# communication_module_20190805.net
KiCad netlist of a schematic drawn in EAGLE
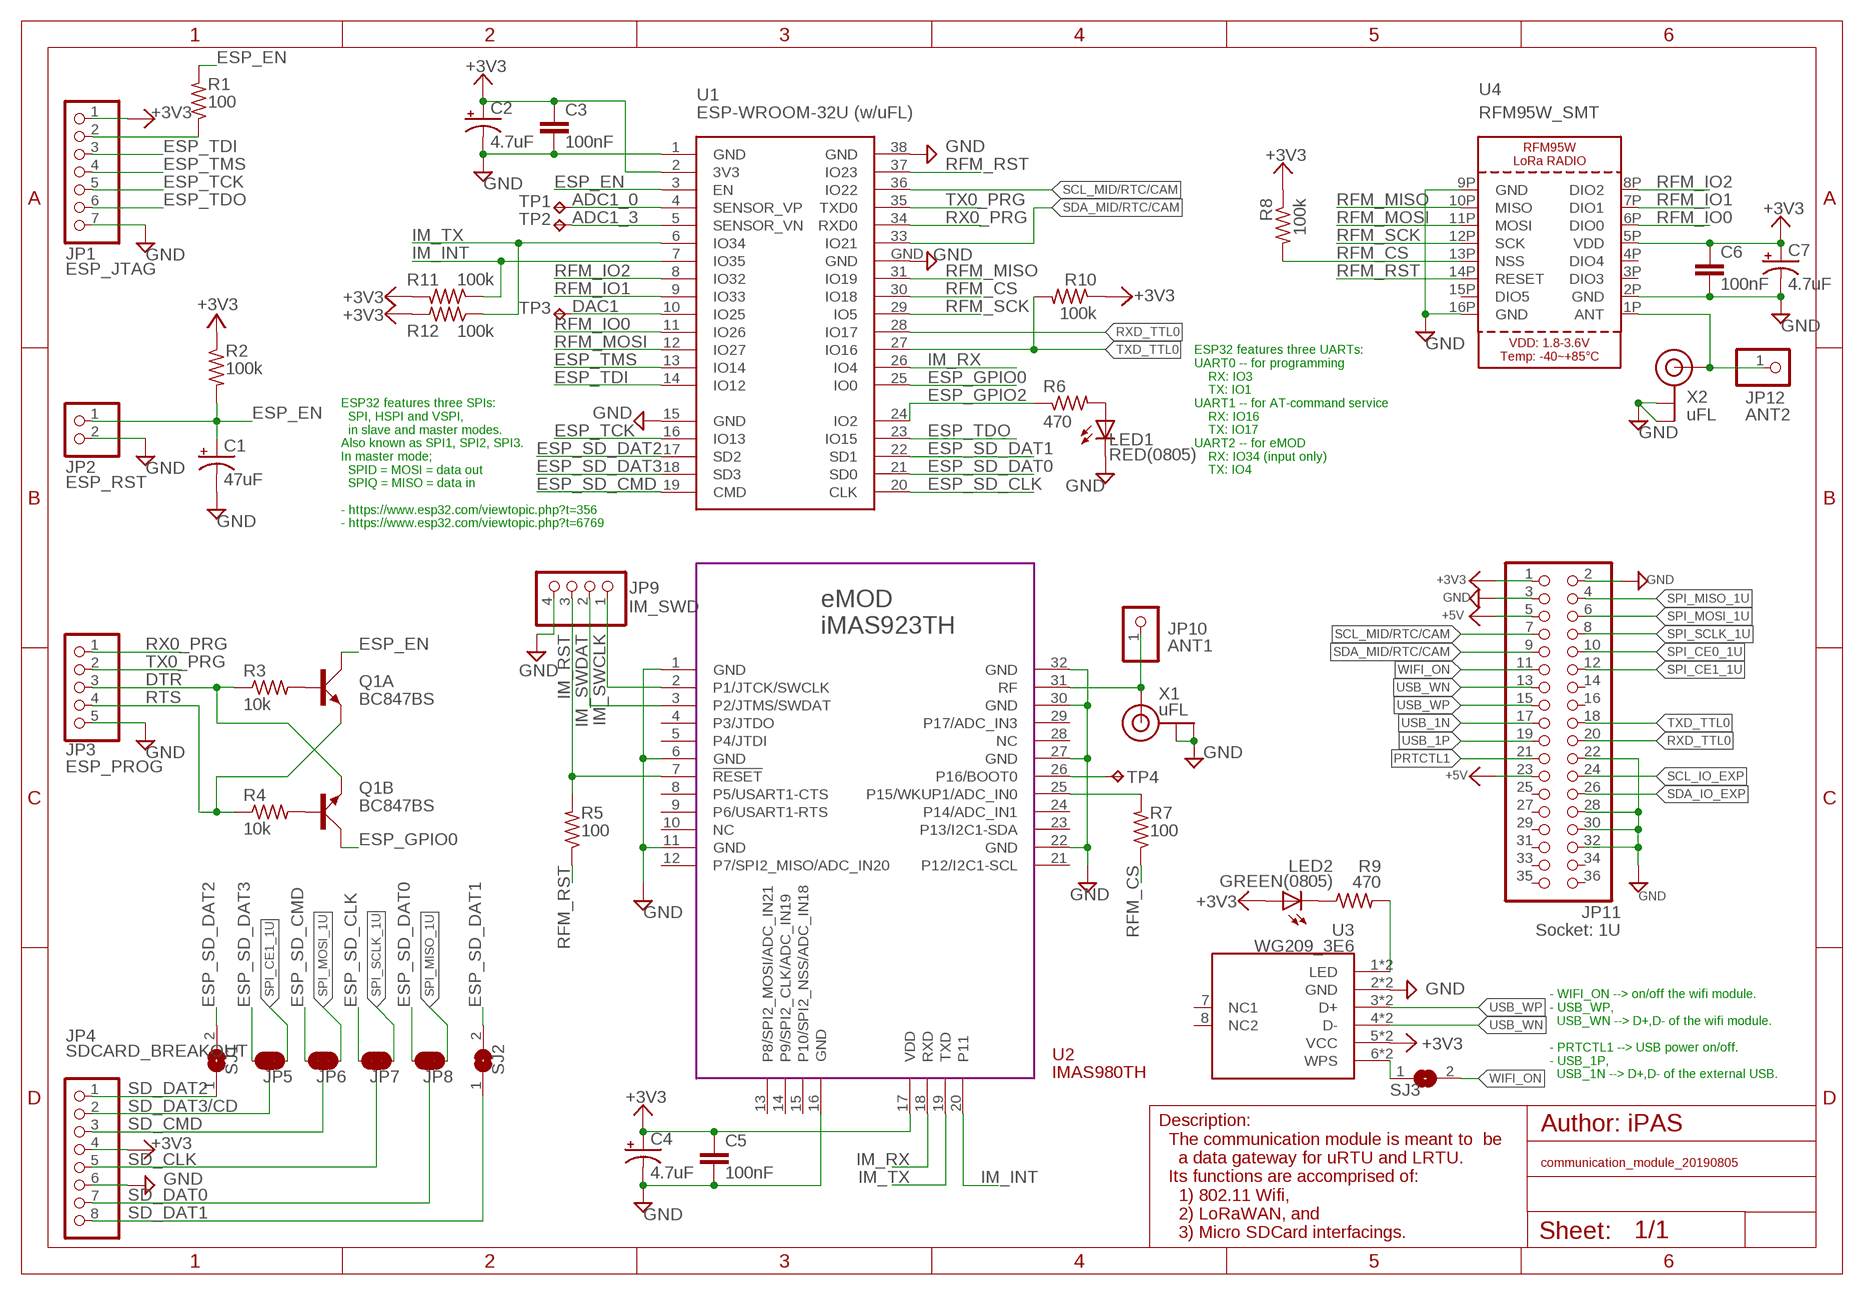
[diagram p0: schematic, sheet 1]

(export (version "E")
  (design (tool "Eeschema 10.0.6"))
  (components
    (comp (ref "C1")
      (value "47uF")
      (footprint "eagle-import:RCL_150CLZ-1014")
      (libsource (lib "eagle-import") (part "RCL_CPOL-US150CLZ-1014"))
    )
    (comp (ref "C2")
      (value "4.7uF")
      (footprint "eagle-import:RCL_150CLZ-1014")
      (libsource (lib "eagle-import") (part "RCL_CPOL-US150CLZ-1014"))
    )
    (comp (ref "C3")
      (value "100nF")
      (footprint "eagle-import:RCL_C1206")
      (libsource (lib "eagle-import") (part "RCL_C-EUC1206"))
    )
    (comp (ref "C4")
      (value "4.7uF")
      (footprint "eagle-import:RCL_150CLZ-1014")
      (libsource (lib "eagle-import") (part "RCL_CPOL-US150CLZ-1014"))
    )
    (comp (ref "C5")
      (value "100nF")
      (footprint "eagle-import:RCL_C1206")
      (libsource (lib "eagle-import") (part "RCL_C-EUC1206"))
    )
    (comp (ref "C6")
      (value "100nF")
      (footprint "eagle-import:RCL_C1206")
      (libsource (lib "eagle-import") (part "RCL_C-EUC1206"))
    )
    (comp (ref "C7")
      (value "4.7uF")
      (footprint "eagle-import:RCL_150CLZ-1014")
      (libsource (lib "eagle-import") (part "RCL_CPOL-US150CLZ-1014"))
    )
    (comp (ref "JP1")
      (value "ESP_JTAG")
      (footprint "eagle-import:1X07")
      (libsource (lib "eagle-import") (part "PINHD-1X7"))
    )
    (comp (ref "JP2")
      (value "ESP_RST")
      (footprint "eagle-import:1X02")
      (libsource (lib "eagle-import") (part "PINHD-1X2"))
    )
    (comp (ref "JP3")
      (value "ESP_PROG")
      (footprint "eagle-import:1X05")
      (libsource (lib "eagle-import") (part "PINHD-1X5"))
    )
    (comp (ref "JP4")
      (value "SDCARD_BREAKOUT")
      (footprint "eagle-import:1X08")
      (libsource (lib "eagle-import") (part "PINHD-1X8"))
    )
    (comp (ref "JP5")
      (value "JUMPER-SMT_3_NO_NO-SILK")
      (footprint "eagle-import:SMT-JUMPER_3_NO_NO-SILK")
      (libsource (lib "eagle-import") (part "JUMPER-SMT_3_NO_NO-SILK"))
    )
    (comp (ref "JP6")
      (value "JUMPER-SMT_3_NO_NO-SILK")
      (footprint "eagle-import:SMT-JUMPER_3_NO_NO-SILK")
      (libsource (lib "eagle-import") (part "JUMPER-SMT_3_NO_NO-SILK"))
    )
    (comp (ref "JP7")
      (value "JUMPER-SMT_3_NO_NO-SILK")
      (footprint "eagle-import:SMT-JUMPER_3_NO_NO-SILK")
      (libsource (lib "eagle-import") (part "JUMPER-SMT_3_NO_NO-SILK"))
    )
    (comp (ref "JP8")
      (value "JUMPER-SMT_3_NO_NO-SILK")
      (footprint "eagle-import:SMT-JUMPER_3_NO_NO-SILK")
      (libsource (lib "eagle-import") (part "JUMPER-SMT_3_NO_NO-SILK"))
    )
    (comp (ref "JP9")
      (value "IM_SWD")
      (footprint "eagle-import:1X04")
      (libsource (lib "eagle-import") (part "PINHD-1X4"))
    )
    (comp (ref "JP10")
      (value "ANT1")
      (footprint "eagle-import:1X01_ROUND")
      (libsource (lib "eagle-import") (part "HEADER-1X1ROUND"))
    )
    (comp (ref "JP11")
      (value "Socket: 1U")
      (footprint "eagle-import:2X18")
      (libsource (lib "eagle-import") (part "PINHD-2X18"))
    )
    (comp (ref "JP12")
      (value "ANT2")
      (footprint "eagle-import:1X01_ROUND")
      (libsource (lib "eagle-import") (part "HEADER-1X1ROUND"))
    )
    (comp (ref "LED1")
      (value "RED(0805)")
      (footprint "eagle-import:CHIP-LED0805")
      (libsource (lib "eagle-import") (part "LEDCHIP-LED0805"))
    )
    (comp (ref "LED2")
      (value "GREEN(0805)")
      (footprint "eagle-import:CHIP-LED0805")
      (libsource (lib "eagle-import") (part "LEDCHIP-LED0805"))
    )
    (comp (ref "Q1")
      (value "BC847BS")
      (footprint "eagle-import:SOT363_PHILIPS")
      (libsource (lib "eagle-import") (part "BC847BS"))
    )
    (comp (ref "R1")
      (value "100")
      (footprint "eagle-import:RCL_M0805")
      (libsource (lib "eagle-import") (part "RCL_R-USM0805"))
    )
    (comp (ref "R2")
      (value "100k")
      (footprint "eagle-import:RCL_M0805")
      (libsource (lib "eagle-import") (part "RCL_R-USM0805"))
    )
    (comp (ref "R3")
      (value "10k")
      (footprint "eagle-import:RCL_M0805")
      (libsource (lib "eagle-import") (part "RCL_R-USM0805"))
    )
    (comp (ref "R4")
      (value "10k")
      (footprint "eagle-import:RCL_M0805")
      (libsource (lib "eagle-import") (part "RCL_R-USM0805"))
    )
    (comp (ref "R5")
      (value "100")
      (footprint "eagle-import:RCL_M0805")
      (libsource (lib "eagle-import") (part "RCL_R-USM0805"))
    )
    (comp (ref "R6")
      (value "470")
      (footprint "eagle-import:RCL_M0805")
      (libsource (lib "eagle-import") (part "RCL_R-USM0805"))
    )
    (comp (ref "R7")
      (value "100")
      (footprint "eagle-import:RCL_M0805")
      (libsource (lib "eagle-import") (part "RCL_R-USM0805"))
    )
    (comp (ref "R8")
      (value "100k")
      (footprint "eagle-import:RCL_M0805")
      (libsource (lib "eagle-import") (part "RCL_R-USM0805"))
    )
    (comp (ref "R9")
      (value "470")
      (footprint "eagle-import:RCL_M0805")
      (libsource (lib "eagle-import") (part "RCL_R-USM0805"))
    )
    (comp (ref "R10")
      (value "100k")
      (footprint "eagle-import:RCL_M0805")
      (libsource (lib "eagle-import") (part "RCL_R-USM0805"))
    )
    (comp (ref "R11")
      (value "100k")
      (footprint "eagle-import:RCL_M0805")
      (libsource (lib "eagle-import") (part "RCL_R-USM0805"))
    )
    (comp (ref "R12")
      (value "100k")
      (footprint "eagle-import:RCL_M0805")
      (libsource (lib "eagle-import") (part "RCL_R-USM0805"))
    )
    (comp (ref "SJ1")
      (value "SOLDERJUMPERREFLOW")
      (footprint "eagle-import:SOLDERJUMPER_REFLOW")
      (libsource (lib "eagle-import") (part "SOLDERJUMPERREFLOW"))
    )
    (comp (ref "SJ2")
      (value "SOLDERJUMPERREFLOW")
      (footprint "eagle-import:SOLDERJUMPER_REFLOW")
      (libsource (lib "eagle-import") (part "SOLDERJUMPERREFLOW"))
    )
    (comp (ref "SJ3")
      (value "SOLDERJUMPERREFLOW")
      (footprint "eagle-import:SOLDERJUMPER_REFLOW")
      (libsource (lib "eagle-import") (part "SOLDERJUMPERREFLOW"))
    )
    (comp (ref "TP1")
      (value "TPB1,27")
      (footprint "eagle-import:B1,27")
      (libsource (lib "eagle-import") (part "TPB1,27"))
    )
    (comp (ref "TP2")
      (value "TPB1,27")
      (footprint "eagle-import:B1,27")
      (libsource (lib "eagle-import") (part "TPB1,27"))
    )
    (comp (ref "TP3")
      (value "TPB1,27")
      (footprint "eagle-import:B1,27")
      (libsource (lib "eagle-import") (part "TPB1,27"))
    )
    (comp (ref "TP4")
      (value "TPB1,27")
      (footprint "eagle-import:B1,27")
      (libsource (lib "eagle-import") (part "TPB1,27"))
    )
    (comp (ref "U1")
      (value "ESP-WROOM-32U (w/uFL)")
      (footprint "eagle-import:ESP-WROOM-32")
      (libsource (lib "eagle-import") (part "ESP-WROOM-32"))
    )
    (comp (ref "U2")
      (value "IMAS980TH")
      (footprint "eagle-import:IMAS923TH")
      (libsource (lib "eagle-import") (part "IMAS980TH"))
    )
    (comp (ref "U3")
      (value "WG209_3E6")
      (footprint "eagle-import:WG209")
      (libsource (lib "eagle-import") (part "WG209"))
    )
    (comp (ref "U4")
      (value "RFM95W_SMT")
      (footprint "eagle-import:RFMHCW_SMT")
      (libsource (lib "eagle-import") (part "RFM95W_SMT"))
    )
    (comp (ref "X1")
      (value "uFL")
      (footprint "eagle-import:U.FL")
      (libsource (lib "eagle-import") (part "ANTENNA_U.FL"))
    )
    (comp (ref "X2")
      (value "uFL")
      (footprint "eagle-import:U.FL")
      (libsource (lib "eagle-import") (part "ANTENNA_U.FL"))
    )
  )
  (nets
    (net (code "1") (name "+3V3") (class "Default")
      (node (ref "C2") (pin "+") (pinfunction "+_+") (pintype "passive"))
      (node (ref "C3") (pin "1") (pinfunction "1_1") (pintype "passive"))
      (node (ref "C4") (pin "+") (pinfunction "+_+") (pintype "passive"))
      (node (ref "C5") (pin "1") (pinfunction "1_1") (pintype "passive"))
      (node (ref "C6") (pin "1") (pinfunction "1_1") (pintype "passive"))
      (node (ref "C7") (pin "+") (pinfunction "+_+") (pintype "passive"))
      (node (ref "JP1") (pin "1") (pinfunction "1_1") (pintype "passive"))
      (node (ref "JP11") (pin "1") (pinfunction "1_1") (pintype "passive"))
      (node (ref "JP4") (pin "4") (pinfunction "4_4") (pintype "passive"))
      (node (ref "LED2") (pin "A") (pinfunction "A_A") (pintype "passive"))
      (node (ref "R10") (pin "1") (pinfunction "1_1") (pintype "passive"))
      (node (ref "R11") (pin "2") (pinfunction "2_2") (pintype "passive"))
      (node (ref "R12") (pin "2") (pinfunction "2_2") (pintype "passive"))
      (node (ref "R2") (pin "1") (pinfunction "1_1") (pintype "passive"))
      (node (ref "R8") (pin "1") (pinfunction "1_1") (pintype "passive"))
      (node (ref "U1") (pin "2") (pinfunction "3V3_2") (pintype "power_in"))
      (node (ref "U2") (pin "17") (pinfunction "VDD_17") (pintype "power_in"))
      (node (ref "U3") (pin "5") (pinfunction "VCC_5") (pintype "power_in"))
      (node (ref "U3") (pin "5P") (pinfunction "VCC_5P") (pintype "power_in"))
      (node (ref "U4") (pin "5P") (pinfunction "VDD_5P") (pintype "power_in"))
    )
    (net (code "2") (name "+5V") (class "Default")
      (node (ref "JP11") (pin "23") (pinfunction "23_23") (pintype "passive"))
      (node (ref "JP11") (pin "5") (pinfunction "5_5") (pintype "passive"))
    )
    (net (code "3") (name "/ADC1_0") (class "Default")
      (node (ref "TP1") (pin "TP") (pinfunction "TP_TP") (pintype "input"))
      (node (ref "U1") (pin "4") (pinfunction "SENSOR_VP_4") (pintype "bidirectional"))
    )
    (net (code "4") (name "/ADC1_3") (class "Default")
      (node (ref "TP2") (pin "TP") (pinfunction "TP_TP") (pintype "input"))
      (node (ref "U1") (pin "5") (pinfunction "SENSOR_VN_5") (pintype "bidirectional"))
    )
    (net (code "5") (name "/DAC1") (class "Default")
      (node (ref "TP3") (pin "TP") (pinfunction "TP_TP") (pintype "input"))
      (node (ref "U1") (pin "10") (pinfunction "IO25_10") (pintype "bidirectional"))
    )
    (net (code "6") (name "/DTR") (class "Default")
      (node (ref "JP3") (pin "3") (pinfunction "3_3") (pintype "passive"))
      (node (ref "Q1") (pin "4") (pinfunction "E_4") (pintype "passive"))
      (node (ref "R3") (pin "1") (pinfunction "1_1") (pintype "passive"))
    )
    (net (code "7") (name "/ESP_EN") (class "Default")
      (node (ref "C1") (pin "+") (pinfunction "+_+") (pintype "passive"))
      (node (ref "JP2") (pin "1") (pinfunction "1_1") (pintype "passive"))
      (node (ref "Q1") (pin "6") (pinfunction "C_6") (pintype "passive"))
      (node (ref "R1") (pin "2") (pinfunction "2_2") (pintype "passive"))
      (node (ref "R2") (pin "2") (pinfunction "2_2") (pintype "passive"))
      (node (ref "U1") (pin "3") (pinfunction "EN_3") (pintype "input"))
    )
    (net (code "8") (name "/ESP_GPIO0") (class "Default")
      (node (ref "Q1") (pin "3") (pinfunction "C_3") (pintype "passive"))
      (node (ref "U1") (pin "25") (pinfunction "IO0_25") (pintype "bidirectional"))
    )
    (net (code "9") (name "/ESP_GPIO2") (class "Default")
      (node (ref "R6") (pin "1") (pinfunction "1_1") (pintype "passive"))
      (node (ref "U1") (pin "24") (pinfunction "IO2_24") (pintype "bidirectional"))
    )
    (net (code "10") (name "/ESP_SD_CLK") (class "Default")
      (node (ref "JP7") (pin "1") (pinfunction "1_1") (pintype "passive"))
      (node (ref "U1") (pin "20") (pinfunction "CLK_20") (pintype "bidirectional"))
    )
    (net (code "11") (name "/ESP_SD_CMD") (class "Default")
      (node (ref "JP6") (pin "1") (pinfunction "1_1") (pintype "passive"))
      (node (ref "U1") (pin "19") (pinfunction "CMD_19") (pintype "bidirectional"))
    )
    (net (code "12") (name "/ESP_SD_DAT0") (class "Default")
      (node (ref "JP8") (pin "1") (pinfunction "1_1") (pintype "passive"))
      (node (ref "U1") (pin "21") (pinfunction "SD0_21") (pintype "bidirectional"))
    )
    (net (code "13") (name "/ESP_SD_DAT1") (class "Default")
      (node (ref "SJ2") (pin "2") (pinfunction "2_2") (pintype "passive"))
      (node (ref "U1") (pin "22") (pinfunction "SD1_22") (pintype "bidirectional"))
    )
    (net (code "14") (name "/ESP_SD_DAT2") (class "Default")
      (node (ref "SJ1") (pin "2") (pinfunction "2_2") (pintype "passive"))
      (node (ref "U1") (pin "17") (pinfunction "SD2_17") (pintype "bidirectional"))
    )
    (net (code "15") (name "/ESP_SD_DAT3") (class "Default")
      (node (ref "JP5") (pin "1") (pinfunction "1_1") (pintype "passive"))
      (node (ref "U1") (pin "18") (pinfunction "SD3_18") (pintype "bidirectional"))
    )
    (net (code "16") (name "/ESP_TCK") (class "Default")
      (node (ref "JP1") (pin "5") (pinfunction "5_5") (pintype "passive"))
      (node (ref "U1") (pin "16") (pinfunction "IO13_16") (pintype "bidirectional"))
    )
    (net (code "17") (name "/ESP_TDI") (class "Default")
      (node (ref "JP1") (pin "3") (pinfunction "3_3") (pintype "passive"))
      (node (ref "U1") (pin "14") (pinfunction "IO12_14") (pintype "bidirectional"))
    )
    (net (code "18") (name "/ESP_TDO") (class "Default")
      (node (ref "JP1") (pin "6") (pinfunction "6_6") (pintype "passive"))
      (node (ref "U1") (pin "23") (pinfunction "IO15_23") (pintype "bidirectional"))
    )
    (net (code "19") (name "/ESP_TMS") (class "Default")
      (node (ref "JP1") (pin "4") (pinfunction "4_4") (pintype "passive"))
      (node (ref "U1") (pin "13") (pinfunction "IO14_13") (pintype "bidirectional"))
    )
    (net (code "20") (name "/IM_INT") (class "Default")
      (node (ref "R11") (pin "1") (pinfunction "1_1") (pintype "passive"))
      (node (ref "U1") (pin "7") (pinfunction "IO35_7") (pintype "bidirectional"))
      (node (ref "U2") (pin "20") (pinfunction "P11_20") (pintype "bidirectional"))
    )
    (net (code "21") (name "/IM_RST") (class "Default")
      (node (ref "JP9") (pin "3") (pinfunction "3_3") (pintype "passive"))
      (node (ref "R5") (pin "2") (pinfunction "2_2") (pintype "passive"))
      (node (ref "U2") (pin "7") (pinfunction "~{RESET}_7") (pintype "passive"))
    )
    (net (code "22") (name "/IM_RX") (class "Default")
      (node (ref "U1") (pin "26") (pinfunction "IO4_26") (pintype "bidirectional"))
      (node (ref "U2") (pin "18") (pinfunction "RXD_18") (pintype "bidirectional"))
    )
    (net (code "23") (name "/IM_SWCLK") (class "Default")
      (node (ref "JP9") (pin "1") (pinfunction "1_1") (pintype "passive"))
      (node (ref "U2") (pin "2") (pinfunction "P1/JTCK/SWCLK_2") (pintype "bidirectional"))
    )
    (net (code "24") (name "/IM_SWDAT") (class "Default")
      (node (ref "JP9") (pin "2") (pinfunction "2_2") (pintype "passive"))
      (node (ref "U2") (pin "3") (pinfunction "P2/JTMS/SWDAT_3") (pintype "bidirectional"))
    )
    (net (code "25") (name "/IM_TX") (class "Default")
      (node (ref "R12") (pin "1") (pinfunction "1_1") (pintype "passive"))
      (node (ref "U1") (pin "6") (pinfunction "IO34_6") (pintype "bidirectional"))
      (node (ref "U2") (pin "19") (pinfunction "TXD_19") (pintype "bidirectional"))
    )
    (net (code "26") (name "/RFM_CS") (class "Default")
      (node (ref "R7") (pin "1") (pinfunction "1_1") (pintype "passive"))
      (node (ref "R8") (pin "2") (pinfunction "2_2") (pintype "passive"))
      (node (ref "U1") (pin "30") (pinfunction "IO18_30") (pintype "bidirectional"))
      (node (ref "U4") (pin "13P") (pinfunction "NSS_13P") (pintype "input"))
    )
    (net (code "27") (name "/RFM_IO0") (class "Default")
      (node (ref "U1") (pin "11") (pinfunction "IO26_11") (pintype "bidirectional"))
      (node (ref "U4") (pin "6P") (pinfunction "DIO0_6P") (pintype "bidirectional"))
    )
    (net (code "28") (name "/RFM_IO1") (class "Default")
      (node (ref "U1") (pin "9") (pinfunction "IO33_9") (pintype "bidirectional"))
      (node (ref "U4") (pin "7P") (pinfunction "DIO1_7P") (pintype "bidirectional"))
    )
    (net (code "29") (name "/RFM_IO2") (class "Default")
      (node (ref "U1") (pin "8") (pinfunction "IO32_8") (pintype "bidirectional"))
      (node (ref "U4") (pin "8P") (pinfunction "DIO2_8P") (pintype "bidirectional"))
    )
    (net (code "30") (name "/RFM_MISO") (class "Default")
      (node (ref "U1") (pin "31") (pinfunction "IO19_31") (pintype "bidirectional"))
      (node (ref "U4") (pin "10P") (pinfunction "MISO_10P") (pintype "output"))
    )
    (net (code "31") (name "/RFM_MOSI") (class "Default")
      (node (ref "U1") (pin "12") (pinfunction "IO27_12") (pintype "bidirectional"))
      (node (ref "U4") (pin "11P") (pinfunction "MOSI_11P") (pintype "input"))
    )
    (net (code "32") (name "/RFM_RST") (class "Default")
      (node (ref "R5") (pin "1") (pinfunction "1_1") (pintype "passive"))
      (node (ref "U1") (pin "37") (pinfunction "IO23_37") (pintype "bidirectional"))
      (node (ref "U4") (pin "14P") (pinfunction "RESET_14P") (pintype "input"))
    )
    (net (code "33") (name "/RFM_SCK") (class "Default")
      (node (ref "U1") (pin "29") (pinfunction "IO5_29") (pintype "bidirectional"))
      (node (ref "U4") (pin "12P") (pinfunction "SCK_12P") (pintype "input"))
    )
    (net (code "34") (name "/RTS") (class "Default")
      (node (ref "JP3") (pin "4") (pinfunction "4_4") (pintype "passive"))
      (node (ref "Q1") (pin "1") (pinfunction "E_1") (pintype "passive"))
      (node (ref "R4") (pin "1") (pinfunction "1_1") (pintype "passive"))
    )
    (net (code "35") (name "/RX0_PRG") (class "Default")
      (node (ref "JP3") (pin "1") (pinfunction "1_1") (pintype "passive"))
      (node (ref "U1") (pin "34") (pinfunction "RXD0_34") (pintype "bidirectional"))
    )
    (net (code "36") (name "/SD_CLK") (class "Default")
      (node (ref "JP4") (pin "5") (pinfunction "5_5") (pintype "passive"))
      (node (ref "JP7") (pin "2") (pinfunction "2_2") (pintype "passive"))
    )
    (net (code "37") (name "/SD_CMD") (class "Default")
      (node (ref "JP4") (pin "3") (pinfunction "3_3") (pintype "passive"))
      (node (ref "JP6") (pin "2") (pinfunction "2_2") (pintype "passive"))
    )
    (net (code "38") (name "/SD_DAT0") (class "Default")
      (node (ref "JP4") (pin "7") (pinfunction "7_7") (pintype "passive"))
      (node (ref "JP8") (pin "2") (pinfunction "2_2") (pintype "passive"))
    )
    (net (code "39") (name "/SD_DAT1") (class "Default")
      (node (ref "JP4") (pin "8") (pinfunction "8_8") (pintype "passive"))
      (node (ref "SJ2") (pin "1") (pinfunction "1_1") (pintype "passive"))
    )
    (net (code "40") (name "/SD_DAT2") (class "Default")
      (node (ref "JP4") (pin "1") (pinfunction "1_1") (pintype "passive"))
      (node (ref "SJ1") (pin "1") (pinfunction "1_1") (pintype "passive"))
    )
    (net (code "41") (name "/SD_DAT3{slash}CD") (class "Default")
      (node (ref "JP4") (pin "2") (pinfunction "2_2") (pintype "passive"))
      (node (ref "JP5") (pin "2") (pinfunction "2_2") (pintype "passive"))
    )
    (net (code "42") (name "/TX0_PRG") (class "Default")
      (node (ref "JP3") (pin "2") (pinfunction "2_2") (pintype "passive"))
      (node (ref "U1") (pin "35") (pinfunction "TXD0_35") (pintype "bidirectional"))
    )
    (net (code "43") (name "GND") (class "Default")
      (node (ref "C1") (pin "-") (pinfunction "-_-") (pintype "passive"))
      (node (ref "C2") (pin "-") (pinfunction "-_-") (pintype "passive"))
      (node (ref "C3") (pin "2") (pinfunction "2_2") (pintype "passive"))
      (node (ref "C4") (pin "-") (pinfunction "-_-") (pintype "passive"))
      (node (ref "C5") (pin "2") (pinfunction "2_2") (pintype "passive"))
      (node (ref "C6") (pin "2") (pinfunction "2_2") (pintype "passive"))
      (node (ref "C7") (pin "-") (pinfunction "-_-") (pintype "passive"))
      (node (ref "JP1") (pin "7") (pinfunction "7_7") (pintype "passive"))
      (node (ref "JP11") (pin "2") (pinfunction "2_2") (pintype "passive"))
      (node (ref "JP11") (pin "22") (pinfunction "22_22") (pintype "passive"))
      (node (ref "JP11") (pin "28") (pinfunction "28_28") (pintype "passive"))
      (node (ref "JP11") (pin "3") (pinfunction "3_3") (pintype "passive"))
      (node (ref "JP11") (pin "30") (pinfunction "30_30") (pintype "passive"))
      (node (ref "JP11") (pin "32") (pinfunction "32_32") (pintype "passive"))
      (node (ref "JP2") (pin "2") (pinfunction "2_2") (pintype "passive"))
      (node (ref "JP3") (pin "5") (pinfunction "5_5") (pintype "passive"))
      (node (ref "JP4") (pin "6") (pinfunction "6_6") (pintype "passive"))
      (node (ref "JP9") (pin "4") (pinfunction "4_4") (pintype "passive"))
      (node (ref "LED1") (pin "C") (pinfunction "C_C") (pintype "passive"))
      (node (ref "U1") (pin "1") (pinfunction "GND_1") (pintype "power_in"))
      (node (ref "U1") (pin "15") (pinfunction "GND_15") (pintype "power_in"))
      (node (ref "U1") (pin "38") (pinfunction "GND_38") (pintype "power_in"))
      (node (ref "U1") (pin "GND") (pinfunction "GND_GND") (pintype "power_in"))
      (node (ref "U2") (pin "1") (pinfunction "GND_1") (pintype "power_in"))
      (node (ref "U2") (pin "11") (pinfunction "GND_11") (pintype "power_in"))
      (node (ref "U2") (pin "16") (pinfunction "GND_16") (pintype "power_in"))
      (node (ref "U2") (pin "22") (pinfunction "GND_22") (pintype "power_in"))
      (node (ref "U2") (pin "27") (pinfunction "GND_27") (pintype "power_in"))
      (node (ref "U2") (pin "30") (pinfunction "GND_30") (pintype "power_in"))
      (node (ref "U2") (pin "32") (pinfunction "GND_32") (pintype "power_in"))
      (node (ref "U2") (pin "6") (pinfunction "GND_6") (pintype "power_in"))
      (node (ref "U3") (pin "2") (pinfunction "GND_2") (pintype "power_in"))
      (node (ref "U3") (pin "2P") (pinfunction "GND_2P") (pintype "power_in"))
      (node (ref "U4") (pin "16P") (pinfunction "GND_16P") (pintype "power_in"))
      (node (ref "U4") (pin "2P") (pinfunction "GND_2P") (pintype "power_in"))
      (node (ref "U4") (pin "9P") (pinfunction "GND_9P") (pintype "power_in"))
      (node (ref "X1") (pin "1") (pinfunction "GND_1") (pintype "passive"))
      (node (ref "X1") (pin "2") (pinfunction "GND_2") (pintype "passive"))
      (node (ref "X2") (pin "1") (pinfunction "GND_1") (pintype "passive"))
      (node (ref "X2") (pin "2") (pinfunction "GND_2") (pintype "passive"))
    )
    (net (code "44") (name "Net-(JP1-Pad2)") (class "Default")
      (node (ref "JP1") (pin "2") (pinfunction "2_2") (pintype "passive"))
      (node (ref "R1") (pin "1") (pinfunction "1_1") (pintype "passive"))
    )
    (net (code "45") (name "Net-(LED1-PadA)") (class "Default")
      (node (ref "LED1") (pin "A") (pinfunction "A_A") (pintype "passive"))
      (node (ref "R6") (pin "2") (pinfunction "2_2") (pintype "passive"))
    )
    (net (code "46") (name "Net-(LED2-PadC)") (class "Default")
      (node (ref "LED2") (pin "C") (pinfunction "C_C") (pintype "passive"))
      (node (ref "R9") (pin "1") (pinfunction "1_1") (pintype "passive"))
    )
    (net (code "47") (name "Net-(Q1A-B)") (class "Default")
      (node (ref "Q1") (pin "2") (pinfunction "B_2") (pintype "passive"))
      (node (ref "R3") (pin "2") (pinfunction "2_2") (pintype "passive"))
    )
    (net (code "48") (name "Net-(Q1B-B)") (class "Default")
      (node (ref "Q1") (pin "5") (pinfunction "B_5") (pintype "passive"))
      (node (ref "R4") (pin "2") (pinfunction "2_2") (pintype "passive"))
    )
    (net (code "49") (name "Net-(R9-Pad2)") (class "Default")
      (node (ref "R9") (pin "2") (pinfunction "2_2") (pintype "passive"))
      (node (ref "U3") (pin "1") (pinfunction "LED_1") (pintype "bidirectional"))
      (node (ref "U3") (pin "1P") (pinfunction "LED_1P") (pintype "bidirectional"))
    )
    (net (code "50") (name "Net-(SJ3-Pad1)") (class "Default")
      (node (ref "SJ3") (pin "1") (pinfunction "1_1") (pintype "passive"))
      (node (ref "U3") (pin "6") (pinfunction "WPS_6") (pintype "bidirectional"))
      (node (ref "U3") (pin "6P") (pinfunction "WPS_6P") (pintype "bidirectional"))
    )
    (net (code "51") (name "Net-(U2-P15{slash}WKUP1{slash}ADC_IN0)") (class "Default")
      (node (ref "R7") (pin "2") (pinfunction "2_2") (pintype "passive"))
      (node (ref "U2") (pin "25") (pinfunction "P15/WKUP1/ADC_IN0_25") (pintype "bidirectional"))
    )
    (net (code "52") (name "Net-(U2-P16{slash}BOOT0)") (class "Default")
      (node (ref "TP4") (pin "TP") (pinfunction "TP_TP") (pintype "input"))
      (node (ref "U2") (pin "26") (pinfunction "P16/BOOT0_26") (pintype "passive"))
    )
    (net (code "53") (name "Net-(U2-RF)") (class "Default")
      (node (ref "JP10") (pin "1") (pinfunction "1_1") (pintype "passive"))
      (node (ref "U2") (pin "31") (pinfunction "RF_31") (pintype "bidirectional"))
      (node (ref "X1") (pin "3") (pinfunction "SIGNAL_3") (pintype "passive"))
    )
    (net (code "54") (name "Net-(U4-ANT)") (class "Default")
      (node (ref "JP12") (pin "1") (pinfunction "1_1") (pintype "passive"))
      (node (ref "U4") (pin "1P") (pinfunction "ANT_1P") (pintype "bidirectional"))
      (node (ref "X2") (pin "3") (pinfunction "SIGNAL_3") (pintype "passive"))
    )
    (net (code "55") (name "PRTCTL1") (class "Default")
      (node (ref "JP11") (pin "21") (pinfunction "21_21") (pintype "passive"))
    )
    (net (code "56") (name "RXD_TTL0") (class "Default")
      (node (ref "JP11") (pin "20") (pinfunction "20_20") (pintype "passive"))
      (node (ref "U1") (pin "28") (pinfunction "IO17_28") (pintype "bidirectional"))
    )
    (net (code "57") (name "SCL_IO_EXP") (class "Default")
      (node (ref "JP11") (pin "24") (pinfunction "24_24") (pintype "passive"))
    )
    (net (code "58") (name "SCL_MID{slash}RTC{slash}CAM") (class "Default")
      (node (ref "JP11") (pin "7") (pinfunction "7_7") (pintype "passive"))
      (node (ref "U1") (pin "36") (pinfunction "IO22_36") (pintype "bidirectional"))
    )
    (net (code "59") (name "SDA_IO_EXP") (class "Default")
      (node (ref "JP11") (pin "26") (pinfunction "26_26") (pintype "passive"))
    )
    (net (code "60") (name "SDA_MID{slash}RTC{slash}CAM") (class "Default")
      (node (ref "JP11") (pin "9") (pinfunction "9_9") (pintype "passive"))
      (node (ref "U1") (pin "33") (pinfunction "IO21_33") (pintype "bidirectional"))
    )
    (net (code "61") (name "SPI_CE0_1U") (class "Default")
      (node (ref "JP11") (pin "10") (pinfunction "10_10") (pintype "passive"))
    )
    (net (code "62") (name "SPI_CE1_1U") (class "Default")
      (node (ref "JP11") (pin "12") (pinfunction "12_12") (pintype "passive"))
      (node (ref "JP5") (pin "3") (pinfunction "3_3") (pintype "passive"))
    )
    (net (code "63") (name "SPI_MISO_1U") (class "Default")
      (node (ref "JP11") (pin "4") (pinfunction "4_4") (pintype "passive"))
      (node (ref "JP8") (pin "3") (pinfunction "3_3") (pintype "passive"))
    )
    (net (code "64") (name "SPI_MOSI_1U") (class "Default")
      (node (ref "JP11") (pin "6") (pinfunction "6_6") (pintype "passive"))
      (node (ref "JP6") (pin "3") (pinfunction "3_3") (pintype "passive"))
    )
    (net (code "65") (name "SPI_SCLK_1U") (class "Default")
      (node (ref "JP11") (pin "8") (pinfunction "8_8") (pintype "passive"))
      (node (ref "JP7") (pin "3") (pinfunction "3_3") (pintype "passive"))
    )
    (net (code "66") (name "TXD_TTL0") (class "Default")
      (node (ref "JP11") (pin "18") (pinfunction "18_18") (pintype "passive"))
      (node (ref "R10") (pin "2") (pinfunction "2_2") (pintype "passive"))
      (node (ref "U1") (pin "27") (pinfunction "IO16_27") (pintype "bidirectional"))
    )
    (net (code "67") (name "USB_1N") (class "Default")
      (node (ref "JP11") (pin "17") (pinfunction "17_17") (pintype "passive"))
    )
    (net (code "68") (name "USB_1P") (class "Default")
      (node (ref "JP11") (pin "19") (pinfunction "19_19") (pintype "passive"))
    )
    (net (code "69") (name "USB_WN") (class "Default")
      (node (ref "JP11") (pin "13") (pinfunction "13_13") (pintype "passive"))
      (node (ref "U3") (pin "4") (pinfunction "D-_4") (pintype "bidirectional"))
      (node (ref "U3") (pin "4P") (pinfunction "D-_4P") (pintype "bidirectional"))
    )
    (net (code "70") (name "USB_WP") (class "Default")
      (node (ref "JP11") (pin "15") (pinfunction "15_15") (pintype "passive"))
      (node (ref "U3") (pin "3") (pinfunction "D+_3") (pintype "bidirectional"))
      (node (ref "U3") (pin "3P") (pinfunction "D+_3P") (pintype "bidirectional"))
    )
    (net (code "71") (name "WIFI_ON") (class "Default")
      (node (ref "JP11") (pin "11") (pinfunction "11_11") (pintype "passive"))
      (node (ref "SJ3") (pin "2") (pinfunction "2_2") (pintype "passive"))
    )
    (net (code "72") (name "unconnected-(JP11-Pad14)") (class "Default")
      (node (ref "JP11") (pin "14") (pinfunction "14_14") (pintype "passive"))
    )
    (net (code "73") (name "unconnected-(JP11-Pad16)") (class "Default")
      (node (ref "JP11") (pin "16") (pinfunction "16_16") (pintype "passive"))
    )
    (net (code "74") (name "unconnected-(JP11-Pad25)") (class "Default")
      (node (ref "JP11") (pin "25") (pinfunction "25_25") (pintype "passive"))
    )
    (net (code "75") (name "unconnected-(JP11-Pad27)") (class "Default")
      (node (ref "JP11") (pin "27") (pinfunction "27_27") (pintype "passive"))
    )
    (net (code "76") (name "unconnected-(JP11-Pad29)") (class "Default")
      (node (ref "JP11") (pin "29") (pinfunction "29_29") (pintype "passive"))
    )
    (net (code "77") (name "unconnected-(JP11-Pad31)") (class "Default")
      (node (ref "JP11") (pin "31") (pinfunction "31_31") (pintype "passive"))
    )
    (net (code "78") (name "unconnected-(JP11-Pad33)") (class "Default")
      (node (ref "JP11") (pin "33") (pinfunction "33_33") (pintype "passive"))
    )
    (net (code "79") (name "unconnected-(JP11-Pad34)") (class "Default")
      (node (ref "JP11") (pin "34") (pinfunction "34_34") (pintype "passive"))
    )
    (net (code "80") (name "unconnected-(JP11-Pad35)") (class "Default")
      (node (ref "JP11") (pin "35") (pinfunction "35_35") (pintype "passive"))
    )
    (net (code "81") (name "unconnected-(JP11-Pad36)") (class "Default")
      (node (ref "JP11") (pin "36") (pinfunction "36_36") (pintype "passive"))
    )
    (net (code "82") (name "unconnected-(U2-NC-Pad10)") (class "Default")
      (node (ref "U2") (pin "10") (pinfunction "NC_10") (pintype "no_connect"))
    )
    (net (code "83") (name "unconnected-(U2-NC-Pad28)") (class "Default")
      (node (ref "U2") (pin "28") (pinfunction "NC_28") (pintype "no_connect"))
    )
    (net (code "84") (name "unconnected-(U2-P3{slash}JTDO-Pad4)") (class "Default")
      (node (ref "U2") (pin "4") (pinfunction "P3/JTDO_4") (pintype "bidirectional"))
    )
    (net (code "85") (name "unconnected-(U2-P4{slash}JTDI-Pad5)") (class "Default")
      (node (ref "U2") (pin "5") (pinfunction "P4/JTDI_5") (pintype "bidirectional"))
    )
    (net (code "86") (name "unconnected-(U2-P5{slash}USART1-CTS-Pad8)") (class "Default")
      (node (ref "U2") (pin "8") (pinfunction "P5/USART1-CTS_8") (pintype "bidirectional"))
    )
    (net (code "87") (name "unconnected-(U2-P6{slash}USART1-RTS-Pad9)") (class "Default")
      (node (ref "U2") (pin "9") (pinfunction "P6/USART1-RTS_9") (pintype "bidirectional"))
    )
    (net (code "88") (name "unconnected-(U2-P7{slash}SPI2_MISO{slash}ADC_IN20-Pad12)") (class "Default")
      (node (ref "U2") (pin "12") (pinfunction "P7/SPI2_MISO/ADC_IN20_12") (pintype "bidirectional"))
    )
    (net (code "89") (name "unconnected-(U2-P8{slash}SPI2_MOSI{slash}ADC_IN21-Pad13)") (class "Default")
      (node (ref "U2") (pin "13") (pinfunction "P8/SPI2_MOSI/ADC_IN21_13") (pintype "bidirectional"))
    )
    (net (code "90") (name "unconnected-(U2-P9{slash}SPI2_CLK{slash}ADC_IN19-Pad14)") (class "Default")
      (node (ref "U2") (pin "14") (pinfunction "P9/SPI2_CLK/ADC_IN19_14") (pintype "bidirectional"))
    )
    (net (code "91") (name "unconnected-(U2-P10{slash}SPI2_NSS{slash}ADC_IN18-Pad15)") (class "Default")
      (node (ref "U2") (pin "15") (pinfunction "P10/SPI2_NSS/ADC_IN18_15") (pintype "bidirectional"))
    )
    (net (code "92") (name "unconnected-(U2-P12{slash}I2C1-SCL-Pad21)") (class "Default")
      (node (ref "U2") (pin "21") (pinfunction "P12/I2C1-SCL_21") (pintype "bidirectional"))
    )
    (net (code "93") (name "unconnected-(U2-P13{slash}I2C1-SDA-Pad23)") (class "Default")
      (node (ref "U2") (pin "23") (pinfunction "P13/I2C1-SDA_23") (pintype "bidirectional"))
    )
    (net (code "94") (name "unconnected-(U2-P14{slash}ADC_IN1-Pad24)") (class "Default")
      (node (ref "U2") (pin "24") (pinfunction "P14/ADC_IN1_24") (pintype "bidirectional"))
    )
    (net (code "95") (name "unconnected-(U2-P17{slash}ADC_IN3-Pad29)") (class "Default")
      (node (ref "U2") (pin "29") (pinfunction "P17/ADC_IN3_29") (pintype "bidirectional"))
    )
    (net (code "96") (name "unconnected-(U3-NC1-Pad7)") (class "Default")
      (node (ref "U3") (pin "7") (pinfunction "NC1_7") (pintype "no_connect"))
    )
    (net (code "97") (name "unconnected-(U3-NC2-Pad8)") (class "Default")
      (node (ref "U3") (pin "8") (pinfunction "NC2_8") (pintype "no_connect"))
    )
    (net (code "98") (name "unconnected-(U4-DIO3-Pad3P)") (class "Default")
      (node (ref "U4") (pin "3P") (pinfunction "DIO3_3P") (pintype "bidirectional"))
    )
    (net (code "99") (name "unconnected-(U4-DIO4-Pad4P)") (class "Default")
      (node (ref "U4") (pin "4P") (pinfunction "DIO4_4P") (pintype "bidirectional"))
    )
    (net (code "100") (name "unconnected-(U4-DIO5-Pad15P)") (class "Default")
      (node (ref "U4") (pin "15P") (pinfunction "DIO5_15P") (pintype "bidirectional"))
    )
  )
)
